# Lagorino_1_1.net
KiCad netlist of a schematic drawn in EAGLE
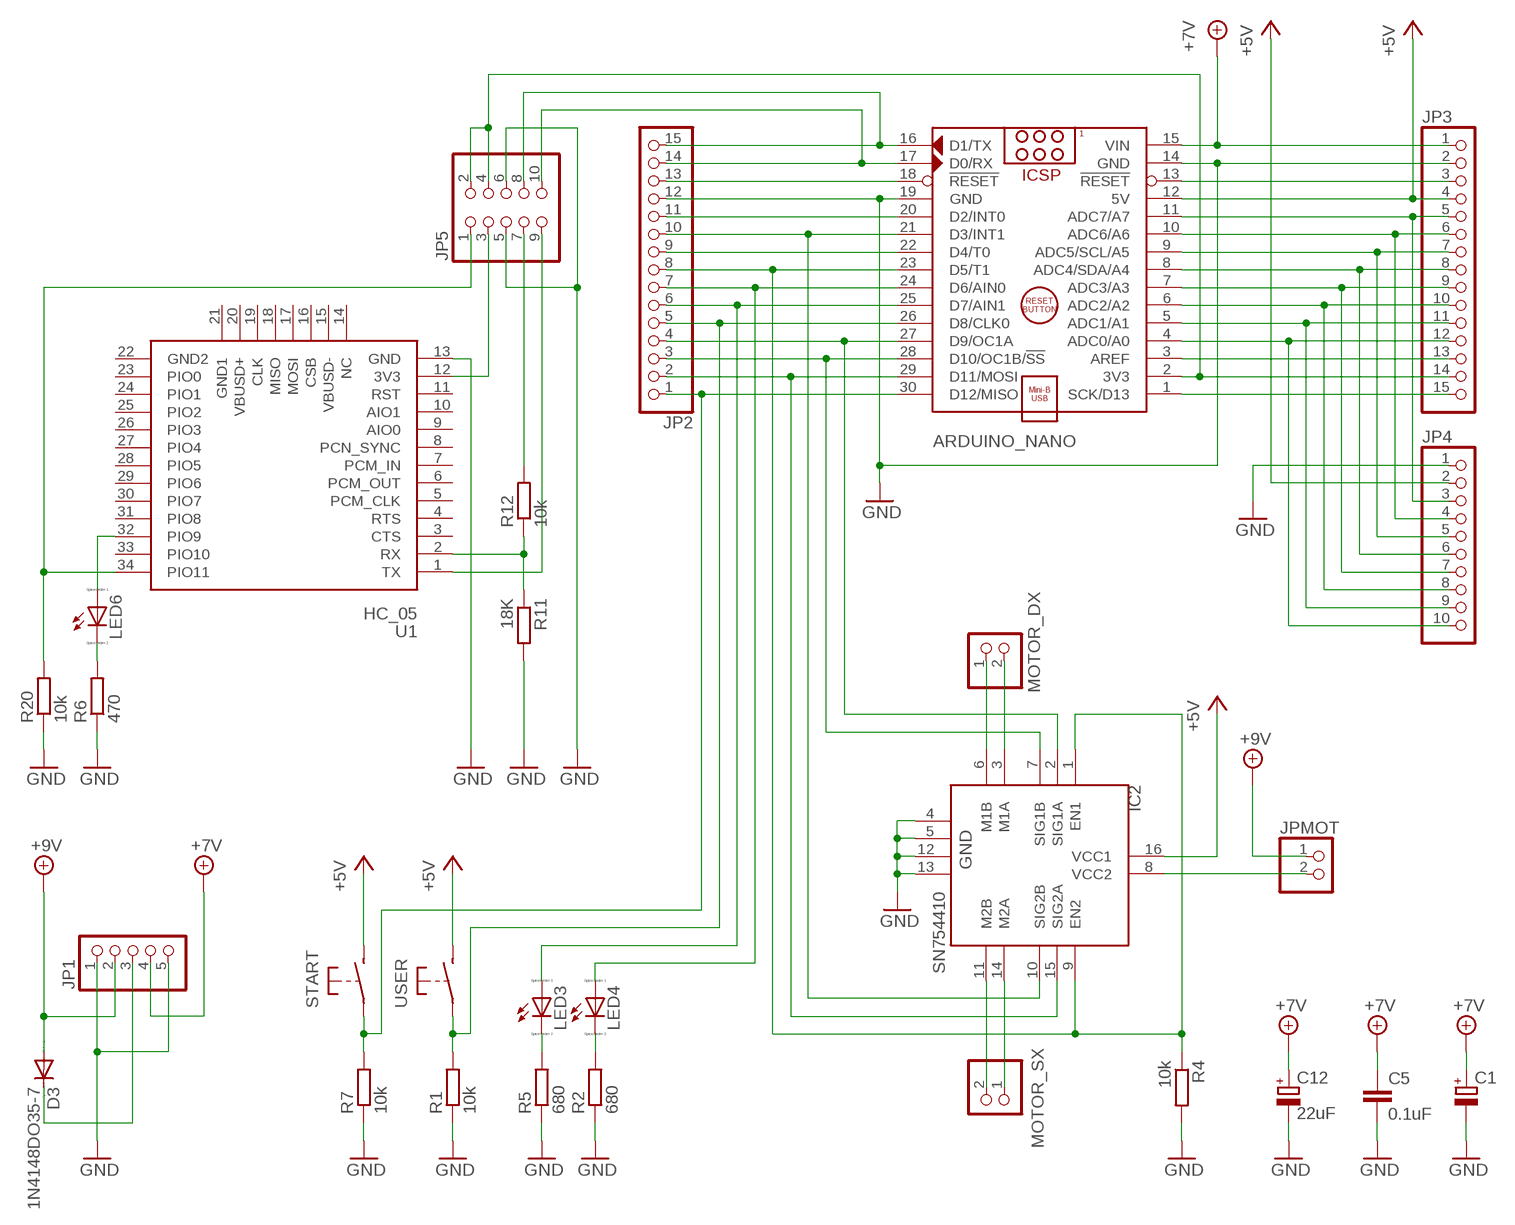
[diagram p0: schematic, sheet 1]

(export (version "E")
  (design (tool "Eeschema 10.0.6"))
  (components
    (comp (ref "ARDUINO_NANO")
      (value "ARDUINO_NANO")
      (footprint "eagle-import:ARDUINO_NANO")
      (libsource (lib "eagle-import") (part "ARDUINO_NANO"))
    )
    (comp (ref "C1")
      (value "CPOL-EUE5-6")
      (footprint "eagle-import:E5-6")
      (libsource (lib "eagle-import") (part "CPOL-EUE5-6"))
    )
    (comp (ref "C5")
      (value "0.1uF")
      (footprint "eagle-import:C0805K")
      (libsource (lib "eagle-import") (part "C-EUC0805K"))
    )
    (comp (ref "C12")
      (value "22uF")
      (footprint "eagle-import:A_3216-18W")
      (libsource (lib "eagle-import") (part "CPOL-EUA/3216-18W"))
    )
    (comp (ref "D3")
      (value "1N4148DO35-7")
      (footprint "eagle-import:DO35-7")
      (libsource (lib "eagle-import") (part "1N4148DO35-7"))
    )
    (comp (ref "IC2")
      (value "SN754410")
      (footprint "eagle-import:DIP16")
      (libsource (lib "eagle-import") (part "SN754410"))
    )
    (comp (ref "JP1")
      (value "PINHD-1X5")
      (footprint "eagle-import:1X05")
      (libsource (lib "eagle-import") (part "PINHD-1X5"))
    )
    (comp (ref "JP2")
      (value "PINHD-1X15")
      (footprint "eagle-import:1X15")
      (libsource (lib "eagle-import") (part "PINHD-1X15"))
    )
    (comp (ref "JP3")
      (value "PINHD-1X15")
      (footprint "eagle-import:1X15")
      (libsource (lib "eagle-import") (part "PINHD-1X15"))
    )
    (comp (ref "JP4")
      (value "PINHD-1X10")
      (footprint "eagle-import:1X10")
      (libsource (lib "eagle-import") (part "PINHD-1X10"))
    )
    (comp (ref "JP5")
      (value "PINHD-2X5")
      (footprint "eagle-import:2X05")
      (libsource (lib "eagle-import") (part "PINHD-2X5"))
    )
    (comp (ref "JPMOT")
      (value "PINHD-1X2")
      (footprint "eagle-import:1X02")
      (libsource (lib "eagle-import") (part "PINHD-1X2"))
    )
    (comp (ref "LED3")
      (value "LED_E")
      (footprint "eagle-import:LED_1206")
      (libsource (lib "eagle-import") (part "LED_E"))
    )
    (comp (ref "LED4")
      (value "LED_E")
      (footprint "eagle-import:LED_1206")
      (libsource (lib "eagle-import") (part "LED_E"))
    )
    (comp (ref "LED6")
      (value "LED_E")
      (footprint "eagle-import:LED_1206")
      (libsource (lib "eagle-import") (part "LED_E"))
    )
    (comp (ref "MOTOR_DX")
      (value "PINHD-1X2")
      (footprint "eagle-import:1X02")
      (libsource (lib "eagle-import") (part "PINHD-1X2"))
    )
    (comp (ref "MOTOR_SX")
      (value "PINHD-1X2")
      (footprint "eagle-import:1X02")
      (libsource (lib "eagle-import") (part "PINHD-1X2"))
    )
    (comp (ref "R1")
      (value "10k")
      (footprint "eagle-import:M0805")
      (libsource (lib "eagle-import") (part "R-EU_M0805"))
    )
    (comp (ref "R2")
      (value "680")
      (footprint "eagle-import:R0805")
      (libsource (lib "eagle-import") (part "R-EU_R0805"))
    )
    (comp (ref "R4")
      (value "10k")
      (footprint "eagle-import:M0805")
      (libsource (lib "eagle-import") (part "R-EU_M0805"))
    )
    (comp (ref "R5")
      (value "680")
      (footprint "eagle-import:R0805")
      (libsource (lib "eagle-import") (part "R-EU_R0805"))
    )
    (comp (ref "R6")
      (value "470")
      (footprint "eagle-import:R0805")
      (libsource (lib "eagle-import") (part "R-EU_R0805"))
    )
    (comp (ref "R7")
      (value "10k")
      (footprint "eagle-import:R0805")
      (libsource (lib "eagle-import") (part "R-EU_R0805"))
    )
    (comp (ref "R11")
      (value "18K")
      (footprint "eagle-import:M0805")
      (libsource (lib "eagle-import") (part "R-EU_M0805"))
    )
    (comp (ref "R12")
      (value "10k")
      (footprint "eagle-import:R0805")
      (libsource (lib "eagle-import") (part "R-EU_R0805"))
    )
    (comp (ref "R20")
      (value "10k")
      (footprint "eagle-import:M0805")
      (libsource (lib "eagle-import") (part "R-EU_M0805"))
    )
    (comp (ref "START")
      (value "SWITCH-MISC_FSM")
      (footprint "eagle-import:SWITCH-MISC_FSM")
      (libsource (lib "eagle-import") (part "SWITCH-MISC_FSM"))
    )
    (comp (ref "U1")
      (value "HC_05")
      (footprint "eagle-import:BLUETOOTH_SMD")
      (libsource (lib "eagle-import") (part "HC_05"))
    )
    (comp (ref "USER")
      (value "SWITCH-MISC_FSM")
      (footprint "eagle-import:SWITCH-MISC_FSM")
      (libsource (lib "eagle-import") (part "SWITCH-MISC_FSM"))
    )
  )
  (nets
    (net (code "1") (name "+5V") (class "Default")
      (node (ref "ARDUINO_NANO") (pin "12") (pinfunction "5V_12") (pintype "power_in"))
      (node (ref "IC2") (pin "16") (pinfunction "VCC1_16") (pintype "power_in"))
      (node (ref "JP3") (pin "4") (pinfunction "4_4") (pintype "passive"))
      (node (ref "JP4") (pin "2") (pinfunction "2_2") (pintype "passive"))
      (node (ref "START") (pin "P$2") (pinfunction "S_P$2") (pintype "passive"))
      (node (ref "USER") (pin "P$2") (pinfunction "S_P$2") (pintype "passive"))
    )
    (net (code "2") (name "+7V") (class "Default")
      (node (ref "ARDUINO_NANO") (pin "15") (pinfunction "VIN_15") (pintype "power_in"))
      (node (ref "C1") (pin "+") (pinfunction "+_+") (pintype "passive"))
      (node (ref "C12") (pin "+") (pinfunction "+_+") (pintype "passive"))
      (node (ref "C5") (pin "1") (pinfunction "1_1") (pintype "passive"))
      (node (ref "JP1") (pin "4") (pinfunction "4_4") (pintype "passive"))
      (node (ref "JP3") (pin "1") (pinfunction "1_1") (pintype "passive"))
    )
    (net (code "3") (name "+9V") (class "Default")
      (node (ref "D3") (pin "A") (pinfunction "A_A") (pintype "passive"))
      (node (ref "JP1") (pin "2") (pinfunction "2_2") (pintype "passive"))
      (node (ref "JPMOT") (pin "1") (pinfunction "1_1") (pintype "passive"))
    )
    (net (code "4") (name "GND") (class "Default")
      (node (ref "ARDUINO_NANO") (pin "14") (pinfunction "GND_14") (pintype "power_in"))
      (node (ref "ARDUINO_NANO") (pin "19") (pinfunction "GND_19") (pintype "power_in"))
      (node (ref "C1") (pin "-") (pinfunction "-_-") (pintype "passive"))
      (node (ref "C12") (pin "-") (pinfunction "-_-") (pintype "passive"))
      (node (ref "C5") (pin "2") (pinfunction "2_2") (pintype "passive"))
      (node (ref "IC2") (pin "12") (pinfunction "P12_12") (pintype "power_in"))
      (node (ref "IC2") (pin "13") (pinfunction "P13_13") (pintype "power_in"))
      (node (ref "IC2") (pin "4") (pinfunction "P4_4") (pintype "power_in"))
      (node (ref "IC2") (pin "5") (pinfunction "P5_5") (pintype "power_in"))
      (node (ref "JP1") (pin "1") (pinfunction "1_1") (pintype "passive"))
      (node (ref "JP1") (pin "5") (pinfunction "5_5") (pintype "passive"))
      (node (ref "JP2") (pin "12") (pinfunction "12_12") (pintype "passive"))
      (node (ref "JP3") (pin "2") (pinfunction "2_2") (pintype "passive"))
      (node (ref "JP4") (pin "1") (pinfunction "1_1") (pintype "passive"))
      (node (ref "JP5") (pin "5") (pinfunction "5_5") (pintype "passive"))
      (node (ref "JP5") (pin "6") (pinfunction "6_6") (pintype "passive"))
      (node (ref "R1") (pin "1") (pinfunction "1_1") (pintype "passive"))
      (node (ref "R11") (pin "2") (pinfunction "2_2") (pintype "passive"))
      (node (ref "R2") (pin "1") (pinfunction "1_1") (pintype "passive"))
      (node (ref "R20") (pin "1") (pinfunction "1_1") (pintype "passive"))
      (node (ref "R4") (pin "2") (pinfunction "2_2") (pintype "passive"))
      (node (ref "R5") (pin "1") (pinfunction "1_1") (pintype "passive"))
      (node (ref "R6") (pin "1") (pinfunction "1_1") (pintype "passive"))
      (node (ref "R7") (pin "1") (pinfunction "1_1") (pintype "passive"))
      (node (ref "U1") (pin "13") (pinfunction "GND_13") (pintype "bidirectional"))
    )
    (net (code "5") (name "Net-(ARDUINO_NANO-3V3)") (class "Default")
      (node (ref "ARDUINO_NANO") (pin "2") (pinfunction "3V3_2") (pintype "output"))
      (node (ref "JP3") (pin "14") (pinfunction "14_14") (pintype "passive"))
      (node (ref "JP5") (pin "2") (pinfunction "2_2") (pintype "passive"))
      (node (ref "JP5") (pin "4") (pinfunction "4_4") (pintype "passive"))
    )
    (net (code "6") (name "Net-(ARDUINO_NANO-ADC0{slash}A0)") (class "Default")
      (node (ref "ARDUINO_NANO") (pin "4") (pinfunction "ADC0/A0_4") (pintype "bidirectional"))
      (node (ref "JP3") (pin "12") (pinfunction "12_12") (pintype "passive"))
      (node (ref "JP4") (pin "10") (pinfunction "10_10") (pintype "passive"))
    )
    (net (code "7") (name "Net-(ARDUINO_NANO-ADC1{slash}A1)") (class "Default")
      (node (ref "ARDUINO_NANO") (pin "5") (pinfunction "ADC1/A1_5") (pintype "bidirectional"))
      (node (ref "JP3") (pin "11") (pinfunction "11_11") (pintype "passive"))
      (node (ref "JP4") (pin "9") (pinfunction "9_9") (pintype "passive"))
    )
    (net (code "8") (name "Net-(ARDUINO_NANO-ADC2{slash}A2)") (class "Default")
      (node (ref "ARDUINO_NANO") (pin "6") (pinfunction "ADC2/A2_6") (pintype "bidirectional"))
      (node (ref "JP3") (pin "10") (pinfunction "10_10") (pintype "passive"))
      (node (ref "JP4") (pin "8") (pinfunction "8_8") (pintype "passive"))
    )
    (net (code "9") (name "Net-(ARDUINO_NANO-ADC3{slash}A3)") (class "Default")
      (node (ref "ARDUINO_NANO") (pin "7") (pinfunction "ADC3/A3_7") (pintype "bidirectional"))
      (node (ref "JP3") (pin "9") (pinfunction "9_9") (pintype "passive"))
      (node (ref "JP4") (pin "7") (pinfunction "7_7") (pintype "passive"))
    )
    (net (code "10") (name "Net-(ARDUINO_NANO-ADC4{slash}SDA{slash}A4)") (class "Default")
      (node (ref "ARDUINO_NANO") (pin "8") (pinfunction "ADC4/SDA/A4_8") (pintype "bidirectional"))
      (node (ref "JP3") (pin "8") (pinfunction "8_8") (pintype "passive"))
      (node (ref "JP4") (pin "6") (pinfunction "6_6") (pintype "passive"))
    )
    (net (code "11") (name "Net-(ARDUINO_NANO-ADC5{slash}SCL{slash}A5)") (class "Default")
      (node (ref "ARDUINO_NANO") (pin "9") (pinfunction "ADC5/SCL/A5_9") (pintype "bidirectional"))
      (node (ref "JP3") (pin "7") (pinfunction "7_7") (pintype "passive"))
      (node (ref "JP4") (pin "5") (pinfunction "5_5") (pintype "passive"))
    )
    (net (code "12") (name "Net-(ARDUINO_NANO-ADC6{slash}A6)") (class "Default")
      (node (ref "ARDUINO_NANO") (pin "10") (pinfunction "ADC6/A6_10") (pintype "bidirectional"))
      (node (ref "JP3") (pin "6") (pinfunction "6_6") (pintype "passive"))
      (node (ref "JP4") (pin "4") (pinfunction "4_4") (pintype "passive"))
    )
    (net (code "13") (name "Net-(ARDUINO_NANO-ADC7{slash}A7)") (class "Default")
      (node (ref "ARDUINO_NANO") (pin "11") (pinfunction "ADC7/A7_11") (pintype "bidirectional"))
      (node (ref "JP3") (pin "5") (pinfunction "5_5") (pintype "passive"))
      (node (ref "JP4") (pin "3") (pinfunction "3_3") (pintype "passive"))
    )
    (net (code "14") (name "Net-(ARDUINO_NANO-AREF)") (class "Default")
      (node (ref "ARDUINO_NANO") (pin "3") (pinfunction "AREF_3") (pintype "input"))
      (node (ref "JP3") (pin "13") (pinfunction "13_13") (pintype "passive"))
    )
    (net (code "15") (name "Net-(ARDUINO_NANO-D0{slash}RX)") (class "Default")
      (node (ref "ARDUINO_NANO") (pin "17") (pinfunction "D0/RX_17") (pintype "bidirectional"))
      (node (ref "JP2") (pin "14") (pinfunction "14_14") (pintype "passive"))
      (node (ref "JP5") (pin "10") (pinfunction "10_10") (pintype "passive"))
    )
    (net (code "16") (name "Net-(ARDUINO_NANO-D1{slash}TX)") (class "Default")
      (node (ref "ARDUINO_NANO") (pin "16") (pinfunction "D1/TX_16") (pintype "bidirectional"))
      (node (ref "JP2") (pin "15") (pinfunction "15_15") (pintype "passive"))
      (node (ref "JP5") (pin "8") (pinfunction "8_8") (pintype "passive"))
    )
    (net (code "17") (name "Net-(ARDUINO_NANO-D2{slash}INT0)") (class "Default")
      (node (ref "ARDUINO_NANO") (pin "20") (pinfunction "D2/INT0_20") (pintype "bidirectional"))
      (node (ref "JP2") (pin "11") (pinfunction "11_11") (pintype "passive"))
    )
    (net (code "18") (name "Net-(ARDUINO_NANO-D3{slash}INT1)") (class "Default")
      (node (ref "ARDUINO_NANO") (pin "21") (pinfunction "D3/INT1_21") (pintype "bidirectional"))
      (node (ref "IC2") (pin "10") (pinfunction "SIG2B_10") (pintype "bidirectional"))
      (node (ref "JP2") (pin "10") (pinfunction "10_10") (pintype "passive"))
    )
    (net (code "19") (name "Net-(ARDUINO_NANO-D4{slash}T0)") (class "Default")
      (node (ref "ARDUINO_NANO") (pin "22") (pinfunction "D4/T0_22") (pintype "bidirectional"))
      (node (ref "JP2") (pin "9") (pinfunction "9_9") (pintype "passive"))
    )
    (net (code "20") (name "Net-(ARDUINO_NANO-D5{slash}T1)") (class "Default")
      (node (ref "ARDUINO_NANO") (pin "23") (pinfunction "D5/T1_23") (pintype "bidirectional"))
      (node (ref "IC2") (pin "1") (pinfunction "EN1_1") (pintype "bidirectional"))
      (node (ref "IC2") (pin "9") (pinfunction "EN2_9") (pintype "bidirectional"))
      (node (ref "JP2") (pin "8") (pinfunction "8_8") (pintype "passive"))
      (node (ref "R4") (pin "1") (pinfunction "1_1") (pintype "passive"))
    )
    (net (code "21") (name "Net-(ARDUINO_NANO-D6{slash}AIN0)") (class "Default")
      (node (ref "ARDUINO_NANO") (pin "24") (pinfunction "D6/AIN0_24") (pintype "bidirectional"))
      (node (ref "JP2") (pin "7") (pinfunction "7_7") (pintype "passive"))
      (node (ref "LED4") (pin "A") (pinfunction "A_A") (pintype "passive"))
    )
    (net (code "22") (name "Net-(ARDUINO_NANO-D7{slash}AIN1)") (class "Default")
      (node (ref "ARDUINO_NANO") (pin "25") (pinfunction "D7/AIN1_25") (pintype "bidirectional"))
      (node (ref "JP2") (pin "6") (pinfunction "6_6") (pintype "passive"))
      (node (ref "LED3") (pin "A") (pinfunction "A_A") (pintype "passive"))
    )
    (net (code "23") (name "Net-(ARDUINO_NANO-D8{slash}CLK0)") (class "Default")
      (node (ref "ARDUINO_NANO") (pin "26") (pinfunction "D8/CLK0_26") (pintype "bidirectional"))
      (node (ref "JP2") (pin "5") (pinfunction "5_5") (pintype "passive"))
      (node (ref "R1") (pin "2") (pinfunction "2_2") (pintype "passive"))
      (node (ref "USER") (pin "P$1") (pinfunction "P_P$1") (pintype "passive"))
    )
    (net (code "24") (name "Net-(ARDUINO_NANO-D9{slash}OC1A)") (class "Default")
      (node (ref "ARDUINO_NANO") (pin "27") (pinfunction "D9/OC1A_27") (pintype "bidirectional"))
      (node (ref "IC2") (pin "2") (pinfunction "SIG1A_2") (pintype "bidirectional"))
      (node (ref "JP2") (pin "4") (pinfunction "4_4") (pintype "passive"))
    )
    (net (code "25") (name "Net-(ARDUINO_NANO-D10{slash}OC1B{slash}~{SS})") (class "Default")
      (node (ref "ARDUINO_NANO") (pin "28") (pinfunction "D10/OC1B/~{SS}_28") (pintype "bidirectional"))
      (node (ref "IC2") (pin "7") (pinfunction "SIG1B_7") (pintype "bidirectional"))
      (node (ref "JP2") (pin "3") (pinfunction "3_3") (pintype "passive"))
    )
    (net (code "26") (name "Net-(ARDUINO_NANO-D11{slash}MOSI)") (class "Default")
      (node (ref "ARDUINO_NANO") (pin "29") (pinfunction "D11/MOSI_29") (pintype "bidirectional"))
      (node (ref "IC2") (pin "15") (pinfunction "SIG2A_15") (pintype "bidirectional"))
      (node (ref "JP2") (pin "2") (pinfunction "2_2") (pintype "passive"))
    )
    (net (code "27") (name "Net-(ARDUINO_NANO-D12{slash}MISO)") (class "Default")
      (node (ref "ARDUINO_NANO") (pin "30") (pinfunction "D12/MISO_30") (pintype "bidirectional"))
      (node (ref "JP2") (pin "1") (pinfunction "1_1") (pintype "passive"))
      (node (ref "R7") (pin "2") (pinfunction "2_2") (pintype "passive"))
      (node (ref "START") (pin "P$1") (pinfunction "P_P$1") (pintype "passive"))
    )
    (net (code "28") (name "Net-(ARDUINO_NANO-SCK{slash}D13)") (class "Default")
      (node (ref "ARDUINO_NANO") (pin "1") (pinfunction "SCK/D13_1") (pintype "bidirectional"))
      (node (ref "JP3") (pin "15") (pinfunction "15_15") (pintype "passive"))
    )
    (net (code "29") (name "Net-(ARDUINO_NANO-~{RESET}-Pad13)") (class "Default")
      (node (ref "ARDUINO_NANO") (pin "13") (pinfunction "~{RESET}_13") (pintype "input"))
      (node (ref "JP3") (pin "3") (pinfunction "3_3") (pintype "passive"))
    )
    (net (code "30") (name "Net-(ARDUINO_NANO-~{RESET}-Pad18)") (class "Default")
      (node (ref "ARDUINO_NANO") (pin "18") (pinfunction "~{RESET}_18") (pintype "input"))
      (node (ref "JP2") (pin "13") (pinfunction "13_13") (pintype "passive"))
    )
    (net (code "31") (name "Net-(D3-PadC)") (class "Default")
      (node (ref "D3") (pin "C") (pinfunction "C_C") (pintype "passive"))
      (node (ref "JP1") (pin "3") (pinfunction "3_3") (pintype "passive"))
    )
    (net (code "32") (name "Net-(IC2-M1A)") (class "Default")
      (node (ref "IC2") (pin "3") (pinfunction "M1A_3") (pintype "bidirectional"))
      (node (ref "MOTOR_DX") (pin "2") (pinfunction "2_2") (pintype "passive"))
    )
    (net (code "33") (name "Net-(IC2-M1B)") (class "Default")
      (node (ref "IC2") (pin "6") (pinfunction "M1B_6") (pintype "bidirectional"))
      (node (ref "MOTOR_DX") (pin "1") (pinfunction "1_1") (pintype "passive"))
    )
    (net (code "34") (name "Net-(IC2-M2A)") (class "Default")
      (node (ref "IC2") (pin "14") (pinfunction "M2A_14") (pintype "bidirectional"))
      (node (ref "MOTOR_SX") (pin "1") (pinfunction "1_1") (pintype "passive"))
    )
    (net (code "35") (name "Net-(IC2-M2B)") (class "Default")
      (node (ref "IC2") (pin "11") (pinfunction "M2B_11") (pintype "bidirectional"))
      (node (ref "MOTOR_SX") (pin "2") (pinfunction "2_2") (pintype "passive"))
    )
    (net (code "36") (name "Net-(IC2-VCC2)") (class "Default")
      (node (ref "IC2") (pin "8") (pinfunction "VCC2_8") (pintype "power_in"))
      (node (ref "JPMOT") (pin "2") (pinfunction "2_2") (pintype "passive"))
    )
    (net (code "37") (name "Net-(JP5-Pad7)") (class "Default")
      (node (ref "JP5") (pin "7") (pinfunction "7_7") (pintype "passive"))
      (node (ref "R12") (pin "2") (pinfunction "2_2") (pintype "passive"))
    )
    (net (code "38") (name "Net-(LED3-PadC)") (class "Default")
      (node (ref "LED3") (pin "C") (pinfunction "C_C") (pintype "passive"))
      (node (ref "R5") (pin "2") (pinfunction "2_2") (pintype "passive"))
    )
    (net (code "39") (name "Net-(LED4-PadC)") (class "Default")
      (node (ref "LED4") (pin "C") (pinfunction "C_C") (pintype "passive"))
      (node (ref "R2") (pin "2") (pinfunction "2_2") (pintype "passive"))
    )
    (net (code "40") (name "Net-(LED6-PadC)") (class "Default")
      (node (ref "LED6") (pin "C") (pinfunction "C_C") (pintype "passive"))
      (node (ref "R6") (pin "2") (pinfunction "2_2") (pintype "passive"))
    )
    (net (code "41") (name "Net-(U1-3V3)") (class "Default")
      (node (ref "JP5") (pin "3") (pinfunction "3_3") (pintype "passive"))
      (node (ref "U1") (pin "12") (pinfunction "3V3_12") (pintype "bidirectional"))
    )
    (net (code "42") (name "Net-(U1-PIO9)") (class "Default")
      (node (ref "LED6") (pin "A") (pinfunction "A_A") (pintype "passive"))
      (node (ref "U1") (pin "32") (pinfunction "PIO9_32") (pintype "bidirectional"))
    )
    (net (code "43") (name "Net-(U1-PIO11)") (class "Default")
      (node (ref "JP5") (pin "1") (pinfunction "1_1") (pintype "passive"))
      (node (ref "R20") (pin "2") (pinfunction "2_2") (pintype "passive"))
      (node (ref "U1") (pin "34") (pinfunction "PIO11_34") (pintype "bidirectional"))
    )
    (net (code "44") (name "Net-(U1-RX)") (class "Default")
      (node (ref "R11") (pin "1") (pinfunction "1_1") (pintype "passive"))
      (node (ref "R12") (pin "1") (pinfunction "1_1") (pintype "passive"))
      (node (ref "U1") (pin "2") (pinfunction "RX_2") (pintype "bidirectional"))
    )
    (net (code "45") (name "Net-(U1-TX)") (class "Default")
      (node (ref "JP5") (pin "9") (pinfunction "9_9") (pintype "passive"))
      (node (ref "U1") (pin "1") (pinfunction "TX_1") (pintype "bidirectional"))
    )
    (net (code "46") (name "unconnected-(U1-AIO0-Pad9)") (class "Default")
      (node (ref "U1") (pin "9") (pinfunction "AIO0_9") (pintype "bidirectional"))
    )
    (net (code "47") (name "unconnected-(U1-AIO1-Pad10)") (class "Default")
      (node (ref "U1") (pin "10") (pinfunction "AIO1_10") (pintype "bidirectional"))
    )
    (net (code "48") (name "unconnected-(U1-CLK-Pad19)") (class "Default")
      (node (ref "U1") (pin "19") (pinfunction "CLK_19") (pintype "bidirectional"))
    )
    (net (code "49") (name "unconnected-(U1-CSB-Pad16)") (class "Default")
      (node (ref "U1") (pin "16") (pinfunction "CSB_16") (pintype "bidirectional"))
    )
    (net (code "50") (name "unconnected-(U1-CTS-Pad3)") (class "Default")
      (node (ref "U1") (pin "3") (pinfunction "CTS_3") (pintype "bidirectional"))
    )
    (net (code "51") (name "unconnected-(U1-GND1-Pad21)") (class "Default")
      (node (ref "U1") (pin "21") (pinfunction "GND1_21") (pintype "bidirectional"))
    )
    (net (code "52") (name "unconnected-(U1-GND2-Pad22)") (class "Default")
      (node (ref "U1") (pin "22") (pinfunction "GND2_22") (pintype "bidirectional"))
    )
    (net (code "53") (name "unconnected-(U1-MISO-Pad18)") (class "Default")
      (node (ref "U1") (pin "18") (pinfunction "MISO_18") (pintype "bidirectional"))
    )
    (net (code "54") (name "unconnected-(U1-MOSI-Pad17)") (class "Default")
      (node (ref "U1") (pin "17") (pinfunction "MOSI_17") (pintype "bidirectional"))
    )
    (net (code "55") (name "unconnected-(U1-NC-Pad14)") (class "Default")
      (node (ref "U1") (pin "14") (pinfunction "NC_14") (pintype "bidirectional"))
    )
    (net (code "56") (name "unconnected-(U1-PCM_CLK-Pad5)") (class "Default")
      (node (ref "U1") (pin "5") (pinfunction "PCM_CLK_5") (pintype "bidirectional"))
    )
    (net (code "57") (name "unconnected-(U1-PCM_IN-Pad7)") (class "Default")
      (node (ref "U1") (pin "7") (pinfunction "PCM_IN_7") (pintype "bidirectional"))
    )
    (net (code "58") (name "unconnected-(U1-PCM_OUT-Pad6)") (class "Default")
      (node (ref "U1") (pin "6") (pinfunction "PCM_OUT_6") (pintype "bidirectional"))
    )
    (net (code "59") (name "unconnected-(U1-PCN_SYNC-Pad8)") (class "Default")
      (node (ref "U1") (pin "8") (pinfunction "PCN_SYNC_8") (pintype "bidirectional"))
    )
    (net (code "60") (name "unconnected-(U1-PIO0-Pad23)") (class "Default")
      (node (ref "U1") (pin "23") (pinfunction "PIO0_23") (pintype "bidirectional"))
    )
    (net (code "61") (name "unconnected-(U1-PIO1-Pad24)") (class "Default")
      (node (ref "U1") (pin "24") (pinfunction "PIO1_24") (pintype "bidirectional"))
    )
    (net (code "62") (name "unconnected-(U1-PIO2-Pad25)") (class "Default")
      (node (ref "U1") (pin "25") (pinfunction "PIO2_25") (pintype "bidirectional"))
    )
    (net (code "63") (name "unconnected-(U1-PIO3-Pad26)") (class "Default")
      (node (ref "U1") (pin "26") (pinfunction "PIO3_26") (pintype "bidirectional"))
    )
    (net (code "64") (name "unconnected-(U1-PIO4-Pad27)") (class "Default")
      (node (ref "U1") (pin "27") (pinfunction "PIO4_27") (pintype "bidirectional"))
    )
    (net (code "65") (name "unconnected-(U1-PIO5-Pad28)") (class "Default")
      (node (ref "U1") (pin "28") (pinfunction "PIO5_28") (pintype "bidirectional"))
    )
    (net (code "66") (name "unconnected-(U1-PIO6-Pad29)") (class "Default")
      (node (ref "U1") (pin "29") (pinfunction "PIO6_29") (pintype "bidirectional"))
    )
    (net (code "67") (name "unconnected-(U1-PIO7-Pad30)") (class "Default")
      (node (ref "U1") (pin "30") (pinfunction "PIO7_30") (pintype "bidirectional"))
    )
    (net (code "68") (name "unconnected-(U1-PIO8-Pad31)") (class "Default")
      (node (ref "U1") (pin "31") (pinfunction "PIO8_31") (pintype "bidirectional"))
    )
    (net (code "69") (name "unconnected-(U1-PIO10-Pad33)") (class "Default")
      (node (ref "U1") (pin "33") (pinfunction "PIO10_33") (pintype "bidirectional"))
    )
    (net (code "70") (name "unconnected-(U1-RST-Pad11)") (class "Default")
      (node (ref "U1") (pin "11") (pinfunction "RST_11") (pintype "bidirectional"))
    )
    (net (code "71") (name "unconnected-(U1-RTS-Pad4)") (class "Default")
      (node (ref "U1") (pin "4") (pinfunction "RTS_4") (pintype "bidirectional"))
    )
    (net (code "72") (name "unconnected-(U1-VBUSD+-Pad20)") (class "Default")
      (node (ref "U1") (pin "20") (pinfunction "VBUSD+_20") (pintype "bidirectional"))
    )
    (net (code "73") (name "unconnected-(U1-VBUSD--Pad15)") (class "Default")
      (node (ref "U1") (pin "15") (pinfunction "VBUSD-_15") (pintype "bidirectional"))
    )
  )
)
